# BMS_Cell_Charging_Adapter_rev1.net
KiCad netlist of a schematic drawn in EAGLE
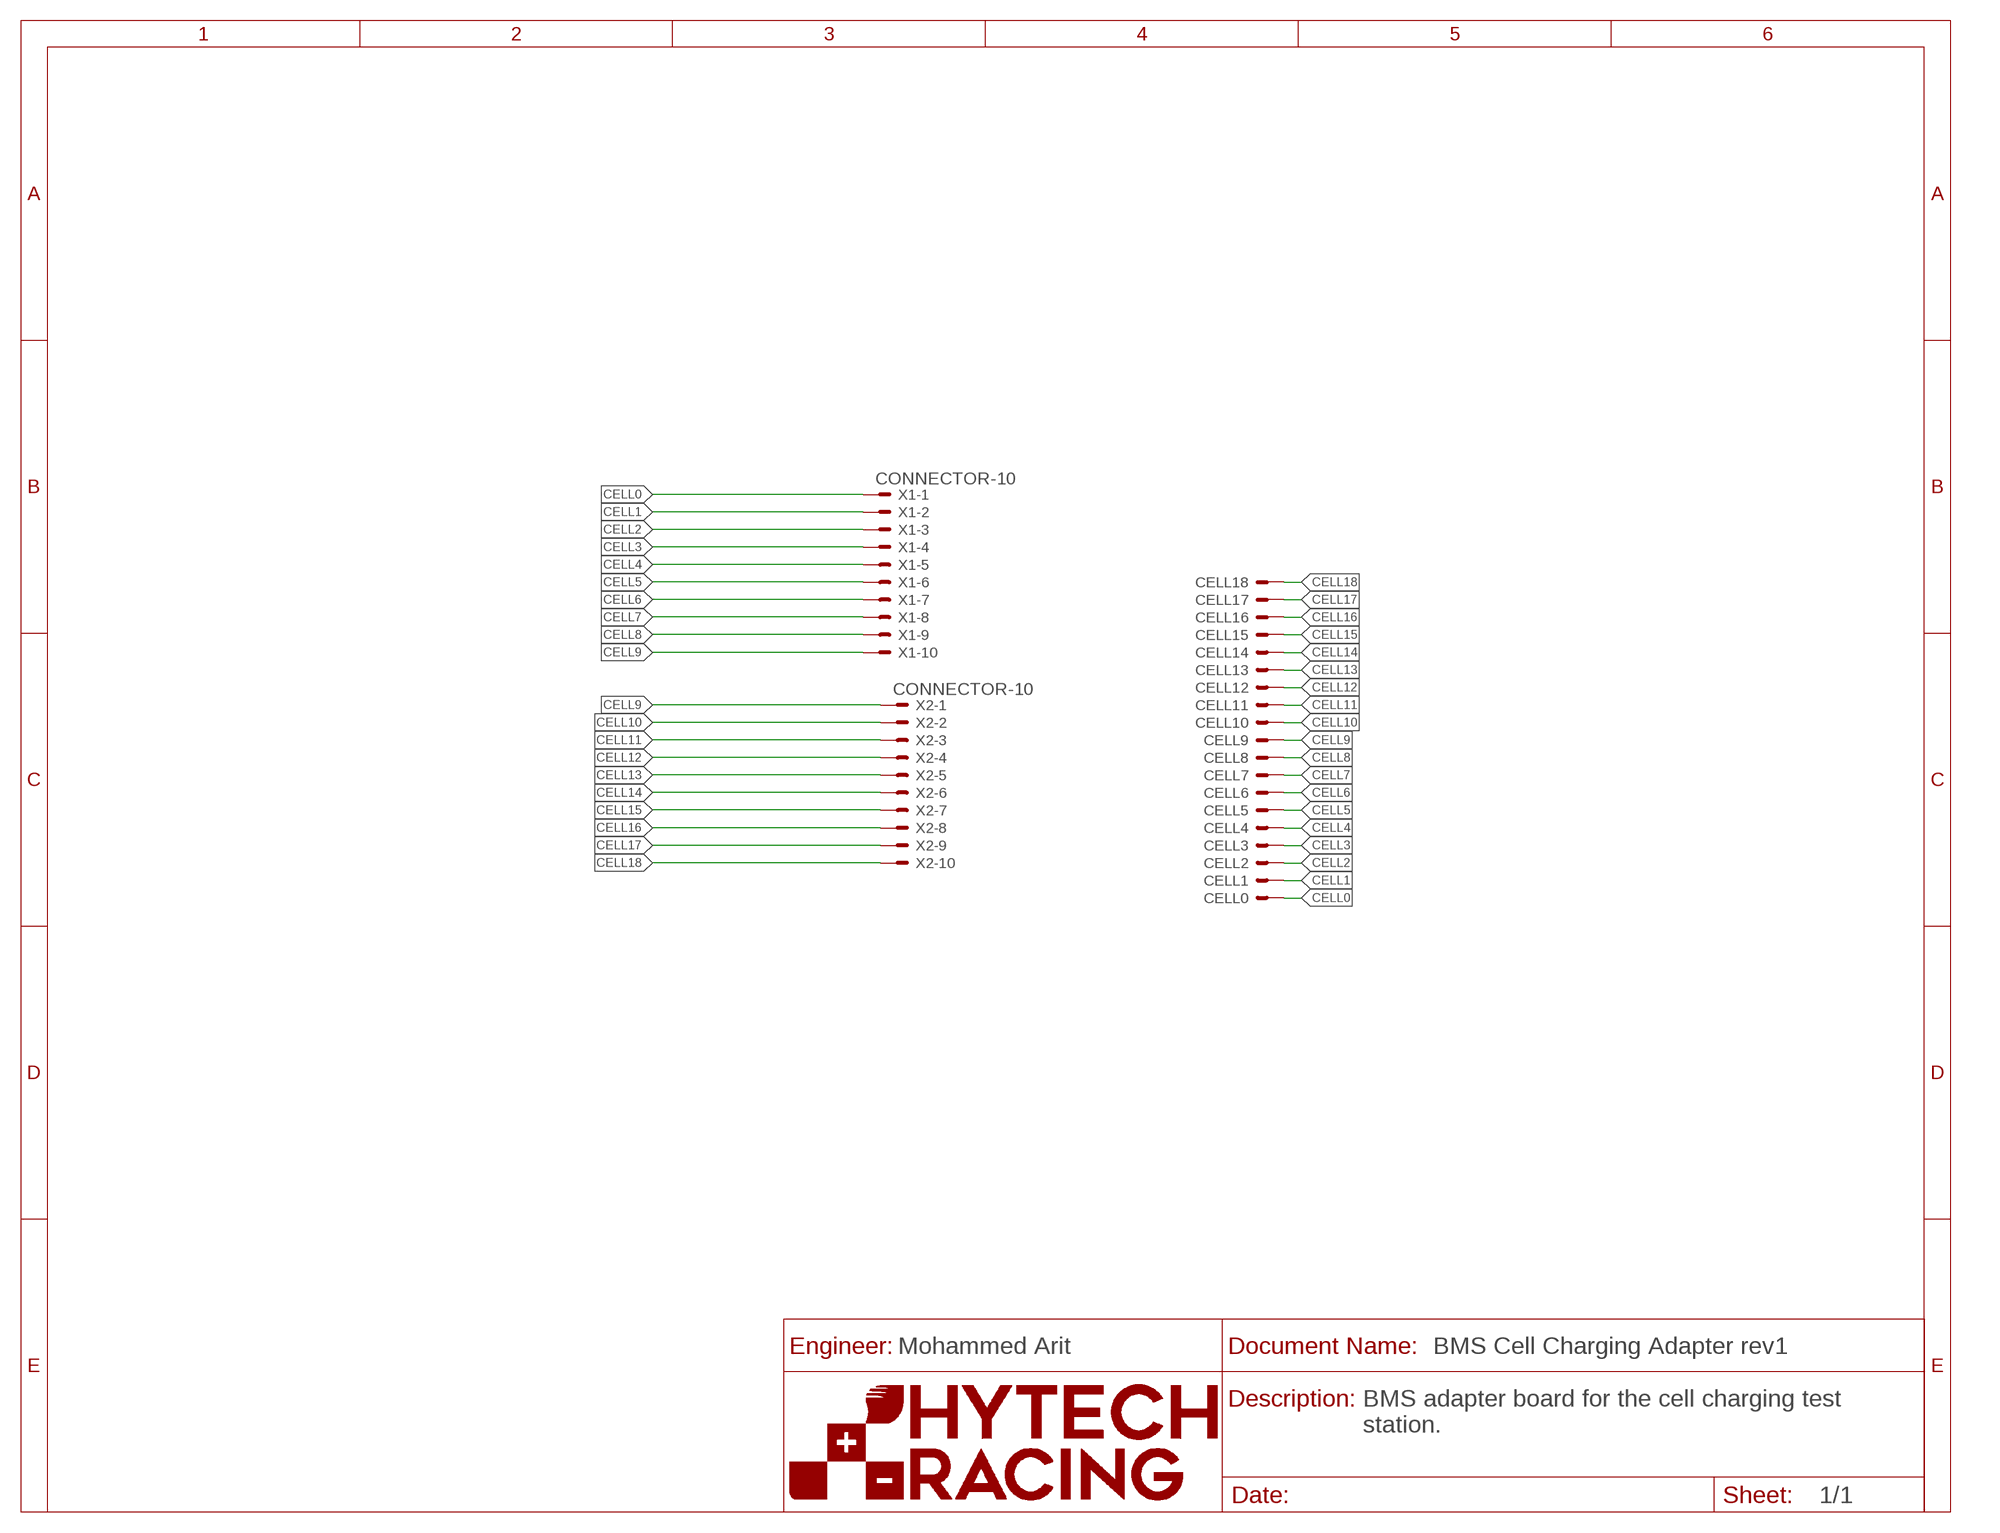
[diagram p0: schematic, sheet 1]

(export (version "E")
  (design (tool "Eeschema 10.0.6"))
  (components
    (comp (ref "CELL0")
      (value "BATTERY_SPRING")
      (footprint "eagle-import:KEYSTONE5203")
      (libsource (lib "eagle-import") (part "BATTERY_SPRING"))
    )
    (comp (ref "CELL1")
      (value "BATTERY_SPRING")
      (footprint "eagle-import:KEYSTONE5203")
      (libsource (lib "eagle-import") (part "BATTERY_SPRING"))
    )
    (comp (ref "CELL2")
      (value "BATTERY_SPRING")
      (footprint "eagle-import:KEYSTONE5203")
      (libsource (lib "eagle-import") (part "BATTERY_SPRING"))
    )
    (comp (ref "CELL3")
      (value "BATTERY_SPRING")
      (footprint "eagle-import:KEYSTONE5203")
      (libsource (lib "eagle-import") (part "BATTERY_SPRING"))
    )
    (comp (ref "CELL4")
      (value "BATTERY_SPRING")
      (footprint "eagle-import:KEYSTONE5203")
      (libsource (lib "eagle-import") (part "BATTERY_SPRING"))
    )
    (comp (ref "CELL5")
      (value "BATTERY_SPRING")
      (footprint "eagle-import:KEYSTONE5203")
      (libsource (lib "eagle-import") (part "BATTERY_SPRING"))
    )
    (comp (ref "CELL6")
      (value "BATTERY_SPRING")
      (footprint "eagle-import:KEYSTONE5203")
      (libsource (lib "eagle-import") (part "BATTERY_SPRING"))
    )
    (comp (ref "CELL7")
      (value "BATTERY_SPRING")
      (footprint "eagle-import:KEYSTONE5203")
      (libsource (lib "eagle-import") (part "BATTERY_SPRING"))
    )
    (comp (ref "CELL8")
      (value "BATTERY_SPRING")
      (footprint "eagle-import:KEYSTONE5203")
      (libsource (lib "eagle-import") (part "BATTERY_SPRING"))
    )
    (comp (ref "CELL9")
      (value "BATTERY_SPRING")
      (footprint "eagle-import:KEYSTONE5203")
      (libsource (lib "eagle-import") (part "BATTERY_SPRING"))
    )
    (comp (ref "CELL10")
      (value "BATTERY_SPRING")
      (footprint "eagle-import:KEYSTONE5203")
      (libsource (lib "eagle-import") (part "BATTERY_SPRING"))
    )
    (comp (ref "CELL11")
      (value "BATTERY_SPRING")
      (footprint "eagle-import:KEYSTONE5203")
      (libsource (lib "eagle-import") (part "BATTERY_SPRING"))
    )
    (comp (ref "CELL12")
      (value "BATTERY_SPRING")
      (footprint "eagle-import:KEYSTONE5203")
      (libsource (lib "eagle-import") (part "BATTERY_SPRING"))
    )
    (comp (ref "CELL13")
      (value "BATTERY_SPRING")
      (footprint "eagle-import:KEYSTONE5203")
      (libsource (lib "eagle-import") (part "BATTERY_SPRING"))
    )
    (comp (ref "CELL14")
      (value "BATTERY_SPRING")
      (footprint "eagle-import:KEYSTONE5203")
      (libsource (lib "eagle-import") (part "BATTERY_SPRING"))
    )
    (comp (ref "CELL15")
      (value "BATTERY_SPRING")
      (footprint "eagle-import:KEYSTONE5203")
      (libsource (lib "eagle-import") (part "BATTERY_SPRING"))
    )
    (comp (ref "CELL16")
      (value "BATTERY_SPRING")
      (footprint "eagle-import:KEYSTONE5203")
      (libsource (lib "eagle-import") (part "BATTERY_SPRING"))
    )
    (comp (ref "CELL17")
      (value "BATTERY_SPRING")
      (footprint "eagle-import:KEYSTONE5203")
      (libsource (lib "eagle-import") (part "BATTERY_SPRING"))
    )
    (comp (ref "CELL18")
      (value "BATTERY_SPRING")
      (footprint "eagle-import:KEYSTONE5203")
      (libsource (lib "eagle-import") (part "BATTERY_SPRING"))
    )
    (comp (ref "X1")
      (value "CONNECTOR-10")
      (footprint "eagle-import:MINIFIT_5566-10")
      (libsource (lib "eagle-import") (part "CONNECTOR-10"))
    )
    (comp (ref "X2")
      (value "CONNECTOR-10")
      (footprint "eagle-import:MINIFIT_5566-10")
      (libsource (lib "eagle-import") (part "CONNECTOR-10"))
    )
  )
  (nets
    (net (code "1") (name "CELL0") (class "Default")
      (node (ref "CELL0") (pin "P$1") (pinfunction "S_P$1") (pintype "passive"))
      (node (ref "X1") (pin "1") (pinfunction "S_1") (pintype "passive"))
    )
    (net (code "2") (name "CELL1") (class "Default")
      (node (ref "CELL1") (pin "P$1") (pinfunction "S_P$1") (pintype "passive"))
      (node (ref "X1") (pin "2") (pinfunction "S_2") (pintype "passive"))
    )
    (net (code "3") (name "CELL2") (class "Default")
      (node (ref "CELL2") (pin "P$1") (pinfunction "S_P$1") (pintype "passive"))
      (node (ref "X1") (pin "3") (pinfunction "S_3") (pintype "passive"))
    )
    (net (code "4") (name "CELL3") (class "Default")
      (node (ref "CELL3") (pin "P$1") (pinfunction "S_P$1") (pintype "passive"))
      (node (ref "X1") (pin "4") (pinfunction "S_4") (pintype "passive"))
    )
    (net (code "5") (name "CELL4") (class "Default")
      (node (ref "CELL4") (pin "P$1") (pinfunction "S_P$1") (pintype "passive"))
      (node (ref "X1") (pin "5") (pinfunction "S_5") (pintype "passive"))
    )
    (net (code "6") (name "CELL5") (class "Default")
      (node (ref "CELL5") (pin "P$1") (pinfunction "S_P$1") (pintype "passive"))
      (node (ref "X1") (pin "6") (pinfunction "S_6") (pintype "passive"))
    )
    (net (code "7") (name "CELL6") (class "Default")
      (node (ref "CELL6") (pin "P$1") (pinfunction "S_P$1") (pintype "passive"))
      (node (ref "X1") (pin "7") (pinfunction "S_7") (pintype "passive"))
    )
    (net (code "8") (name "CELL7") (class "Default")
      (node (ref "CELL7") (pin "P$1") (pinfunction "S_P$1") (pintype "passive"))
      (node (ref "X1") (pin "8") (pinfunction "S_8") (pintype "passive"))
    )
    (net (code "9") (name "CELL8") (class "Default")
      (node (ref "CELL8") (pin "P$1") (pinfunction "S_P$1") (pintype "passive"))
      (node (ref "X1") (pin "9") (pinfunction "S_9") (pintype "passive"))
    )
    (net (code "10") (name "CELL9") (class "Default")
      (node (ref "CELL9") (pin "P$1") (pinfunction "S_P$1") (pintype "passive"))
      (node (ref "X1") (pin "10") (pinfunction "S_10") (pintype "passive"))
      (node (ref "X2") (pin "1") (pinfunction "S_1") (pintype "passive"))
    )
    (net (code "11") (name "CELL10") (class "Default")
      (node (ref "CELL10") (pin "P$1") (pinfunction "S_P$1") (pintype "passive"))
      (node (ref "X2") (pin "2") (pinfunction "S_2") (pintype "passive"))
    )
    (net (code "12") (name "CELL11") (class "Default")
      (node (ref "CELL11") (pin "P$1") (pinfunction "S_P$1") (pintype "passive"))
      (node (ref "X2") (pin "3") (pinfunction "S_3") (pintype "passive"))
    )
    (net (code "13") (name "CELL12") (class "Default")
      (node (ref "CELL12") (pin "P$1") (pinfunction "S_P$1") (pintype "passive"))
      (node (ref "X2") (pin "4") (pinfunction "S_4") (pintype "passive"))
    )
    (net (code "14") (name "CELL13") (class "Default")
      (node (ref "CELL13") (pin "P$1") (pinfunction "S_P$1") (pintype "passive"))
      (node (ref "X2") (pin "5") (pinfunction "S_5") (pintype "passive"))
    )
    (net (code "15") (name "CELL14") (class "Default")
      (node (ref "CELL14") (pin "P$1") (pinfunction "S_P$1") (pintype "passive"))
      (node (ref "X2") (pin "6") (pinfunction "S_6") (pintype "passive"))
    )
    (net (code "16") (name "CELL15") (class "Default")
      (node (ref "CELL15") (pin "P$1") (pinfunction "S_P$1") (pintype "passive"))
      (node (ref "X2") (pin "7") (pinfunction "S_7") (pintype "passive"))
    )
    (net (code "17") (name "CELL16") (class "Default")
      (node (ref "CELL16") (pin "P$1") (pinfunction "S_P$1") (pintype "passive"))
      (node (ref "X2") (pin "8") (pinfunction "S_8") (pintype "passive"))
    )
    (net (code "18") (name "CELL17") (class "Default")
      (node (ref "CELL17") (pin "P$1") (pinfunction "S_P$1") (pintype "passive"))
      (node (ref "X2") (pin "9") (pinfunction "S_9") (pintype "passive"))
    )
    (net (code "19") (name "CELL18") (class "Default")
      (node (ref "CELL18") (pin "P$1") (pinfunction "S_P$1") (pintype "passive"))
      (node (ref "X2") (pin "10") (pinfunction "S_10") (pintype "passive"))
    )
  )
)
